# Analog_project.net
KiCad netlist of a schematic drawn in Altium Designer
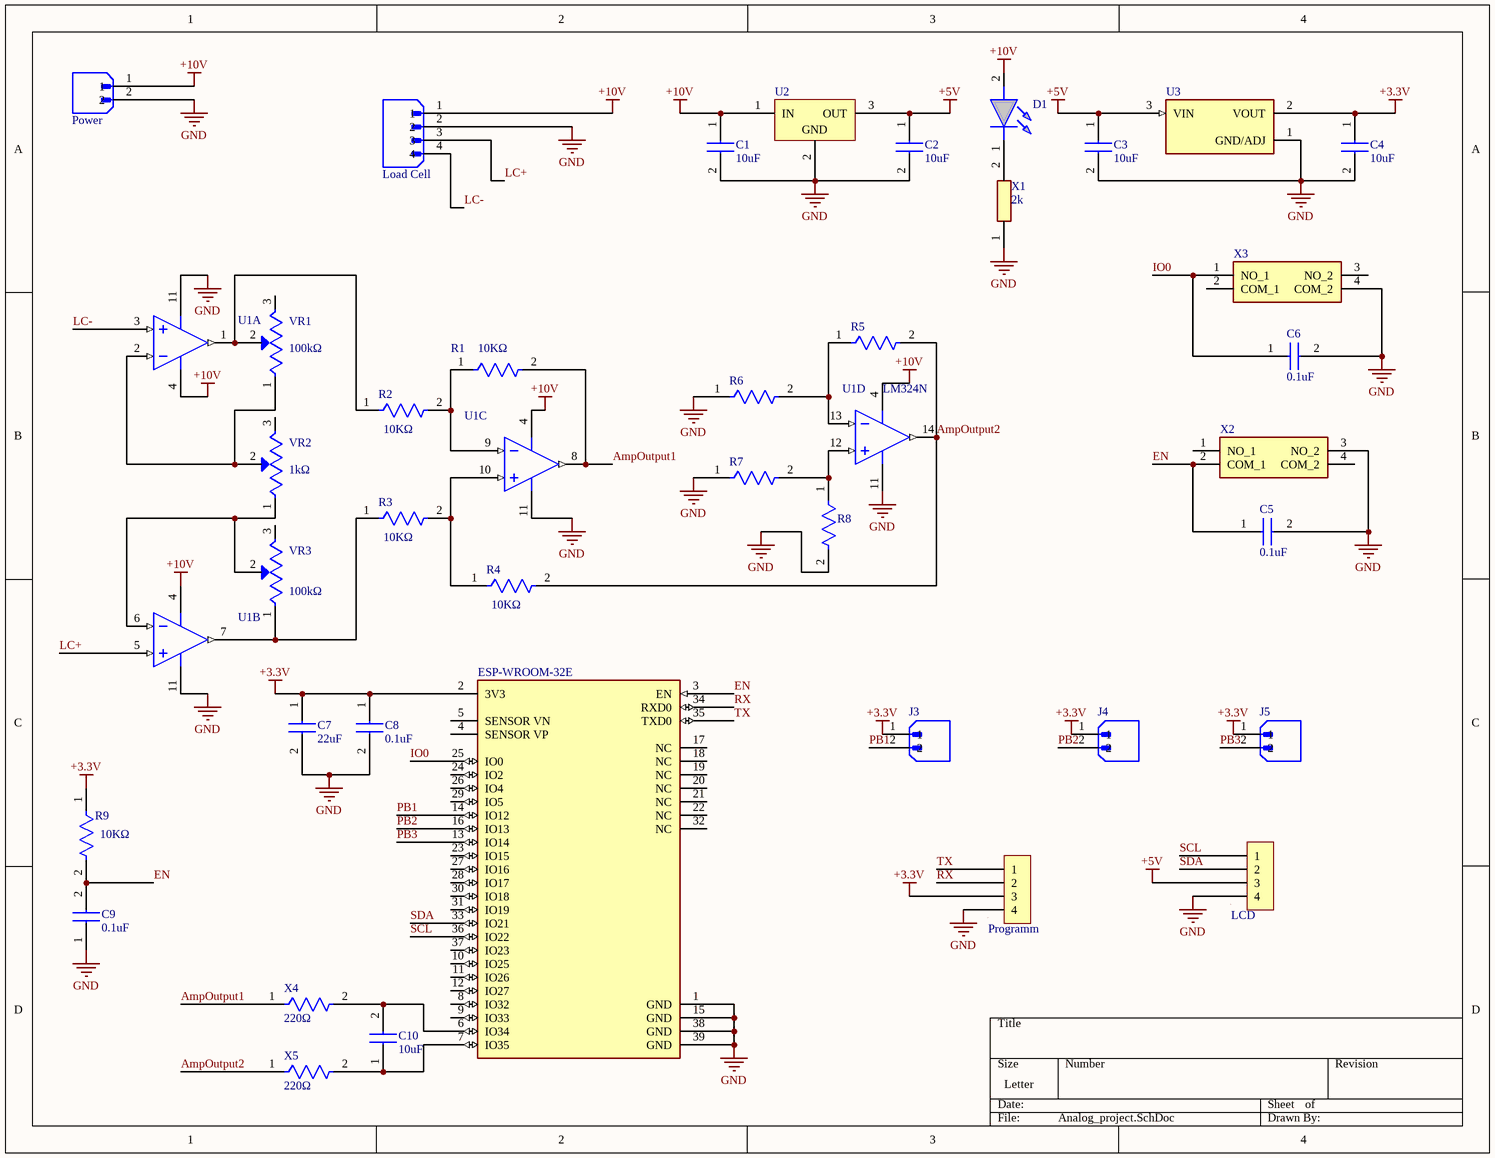
[diagram p0: Analog_project.SchDoc]

(export (version "E")
  (design (tool "Eeschema 10.0.6"))
  (components
    (comp (ref "C1")
      (value "C1206C106K8RAC")
      (footprint "CAPC3216X180N")
      (description "Multilayer Ceramic Capacitors MLCC - SMD/SMT 10V 10uF X7R 1206 0.1")
      (fields (field (name "MOUSER PART NUMBER") "80-C1206C106K8RAC") (field (name "CAPACITANCE") "10uF"))
      (libsource (lib "Analog_project") (part "C1206C106K8RAC"))
    )
    (comp (ref "C2")
      (value "C1206C106K8RAC")
      (footprint "CAPC3216X180N")
      (description "Multilayer Ceramic Capacitors MLCC - SMD/SMT 10V 10uF X7R 1206 0.1")
      (fields (field (name "MOUSER PART NUMBER") "80-C1206C106K8RAC") (field (name "CAPACITANCE") "10uF"))
      (libsource (lib "Analog_project") (part "C1206C106K8RAC"))
    )
    (comp (ref "C3")
      (value "C1206C106K8RAC")
      (footprint "CAPC3216X180N")
      (description "Multilayer Ceramic Capacitors MLCC - SMD/SMT 10V 10uF X7R 1206 0.1")
      (fields (field (name "MOUSER PART NUMBER") "80-C1206C106K8RAC") (field (name "CAPACITANCE") "10uF"))
      (libsource (lib "Analog_project") (part "C1206C106K8RAC"))
    )
    (comp (ref "C4")
      (value "C1206C106K8RAC")
      (footprint "CAPC3216X180N")
      (description "Multilayer Ceramic Capacitors MLCC - SMD/SMT 10V 10uF X7R 1206 0.1")
      (fields (field (name "MOUSER PART NUMBER") "80-C1206C106K8RAC") (field (name "CAPACITANCE") "10uF"))
      (libsource (lib "Analog_project") (part "C1206C106K8RAC"))
    )
    (comp (ref "C5")
      (value "C1206C104K5RAC7867")
      (footprint "CAPC3216X110N")
      (description "Multilayer Ceramic Capacitors MLCC - SMD/SMT 50V 0.1uF X7R 1206 10%")
      (fields (field (name "MOUSER PART NUMBER") "80-C1206104K5RAC7867") (field (name "CAPACITANCE") "0.1uF"))
      (libsource (lib "Analog_project") (part "C1206C104K5RAC7867"))
    )
    (comp (ref "C6")
      (value "C1206C104K5RAC7867")
      (footprint "CAPC3216X110N")
      (description "Multilayer Ceramic Capacitors MLCC - SMD/SMT 50V 0.1uF X7R 1206 10%")
      (fields (field (name "MOUSER PART NUMBER") "80-C1206104K5RAC7867") (field (name "CAPACITANCE") "0.1uF"))
      (libsource (lib "Analog_project") (part "C1206C104K5RAC7867"))
    )
    (comp (ref "C7")
      (value "CL31B226KPKVPJE")
      (footprint "CAPC2012X150N")
      (description "General Multilayer Ceramic Capacitors")
      (fields (field (name "MOUSER PART NUMBER") "187-CL31B226KPKVPJE") (field (name "CAPACITAMCE") "22uF"))
      (libsource (lib "Analog_project") (part "CL31B226KPKVPJE"))
    )
    (comp (ref "C8")
      (value "C1206C104K5RAC7867")
      (footprint "CAPC3216X110N")
      (description "Multilayer Ceramic Capacitors MLCC - SMD/SMT 50V 0.1uF X7R 1206 10%")
      (fields (field (name "MOUSER PART NUMBER") "80-C1206104K5RAC7867") (field (name "CAPACITANCE") "0.1uF"))
      (libsource (lib "Analog_project") (part "C1206C104K5RAC7867"))
    )
    (comp (ref "C9")
      (value "C1206C104K5RAC7867")
      (footprint "CAPC3216X110N")
      (description "Multilayer Ceramic Capacitors MLCC - SMD/SMT 50V 0.1uF X7R 1206 10%")
      (fields (field (name "MOUSER PART NUMBER") "80-C1206104K5RAC7867") (field (name "CAPACITANCE") "0.1uF"))
      (libsource (lib "Analog_project") (part "C1206C104K5RAC7867"))
    )
    (comp (ref "C10")
      (value "C1206C106K8RAC")
      (footprint "CAPC3216X180N")
      (description "Multilayer Ceramic Capacitors MLCC - SMD/SMT 10V 10uF X7R 1206 0.1")
      (fields (field (name "MOUSER PART NUMBER") "80-C1206C106K8RAC") (field (name "CAPACITANCE") "10uF"))
      (libsource (lib "Analog_project") (part "C1206C106K8RAC"))
    )
    (comp (ref "D1")
      (value "150120GS75000")
      (footprint "LEDC3214X78N")
      (fields (field (name "MOUSER PART NUMBER") "710-150120GS75000"))
      (libsource (lib "Analog_project") (part "150120GS75000"))
    )
    (comp (ref "ESP-WROOM-32E")
      (value "ESP32-WROOM-32E (16MB)")
      (footprint "FP-ESP32-WROOM-32E_16MB-MFG")
      (description "RX TXRX MOD WIFI TRACE ANT SMD")
      (libsource (lib "Analog_project") (part "CMP-194065-000027-1"))
    )
    (comp (ref "J3")
      (value "B2B-XH-A(LF)(SN)")
      (footprint "JST_B2B-XH-A(LF)(SN)")
      (description "Connector Header Through Hole 2 position 0.098 (2.50mm)")
      (fields (field (name "MF") "JST Sales America Inc."))
      (libsource (lib "") (part "B2B-XH-A(LF)(SN)_1"))
    )
    (comp (ref "J4")
      (value "B2B-XH-A(LF)(SN)")
      (footprint "JST_B2B-XH-A(LF)(SN)")
      (description "Connector Header Through Hole 2 position 0.098 (2.50mm)")
      (fields (field (name "MF") "JST Sales America Inc."))
      (libsource (lib "") (part "B2B-XH-A(LF)(SN)_1"))
    )
    (comp (ref "J5")
      (value "B2B-XH-A(LF)(SN)")
      (footprint "JST_B2B-XH-A(LF)(SN)")
      (description "Connector Header Through Hole 2 position 0.098 (2.50mm)")
      (fields (field (name "MF") "JST Sales America Inc."))
      (libsource (lib "") (part "B2B-XH-A(LF)(SN)_1"))
    )
    (comp (ref "LCD")
      (value "61300411121")
      (footprint "61300411121")
      (fields (field (name "MANUFACTURER") "Wurth Electronics"))
      (libsource (lib "Analog_project") (part "61300411121"))
    )
    (comp (ref "Load Cell")
      (value "B4B-XH-A(LF)(SN)")
      (footprint "JST_B4B-XH-A(LF)(SN)")
      (description "Connector Header Through Hole 4 position 0.098 (2.50mm)")
      (fields (field (name "MF") "JST Sales"))
      (libsource (lib "Analog_project") (part "B4B-XH-A(LF)(SN)"))
    )
    (comp (ref "Power")
      (value "B2B-XH-A(LF)(SN)")
      (footprint "JST_B2B-XH-A(LF)(SN)")
      (description "Connector Header Through Hole 2 position 0.098 (2.50mm)")
      (fields (field (name "MF") "JST Sales America Inc."))
      (libsource (lib "Analog_project") (part "B2B-XH-A(LF)(SN)"))
    )
    (comp (ref "Programm")
      (value "61300411121")
      (footprint "61300411121")
      (fields (field (name "MANUFACTURER") "Wurth Electronics"))
      (libsource (lib "Analog_project") (part "61300411121"))
    )
    (comp (ref "R1")
      (value "10KΩ")
      (footprint "FP-CRGP1210-IPC_A")
      (description "CRGP1210 10KΩ 0.75W ±100ppm/°C 1% 200V")
      (fields
        (field (name "TOLERANCE") "0.01")
        (field (name "OCTOPART") "https://octopart.com/crgp1210f10k-te+connectivity-91018904")
      )
      (libsource (lib "Analog_project") (part "CMP-03211-008532-1"))
    )
    (comp (ref "R2")
      (value "10KΩ")
      (footprint "FP-CRGP1210-IPC_A")
      (description "CRGP1210 10KΩ 0.75W ±100ppm/°C 1% 200V")
      (fields
        (field (name "TOLERANCE") "0.01")
        (field (name "OCTOPART") "https://octopart.com/crgp1210f10k-te+connectivity-91018904")
      )
      (libsource (lib "Analog_project") (part "CMP-03211-008532-1"))
    )
    (comp (ref "R3")
      (value "10KΩ")
      (footprint "FP-CRGP1210-IPC_A")
      (description "CRGP1210 10KΩ 0.75W ±100ppm/°C 1% 200V")
      (fields
        (field (name "TOLERANCE") "0.01")
        (field (name "OCTOPART") "https://octopart.com/crgp1210f10k-te+connectivity-91018904")
      )
      (libsource (lib "Analog_project") (part "CMP-03211-008532-1"))
    )
    (comp (ref "R4")
      (value "10KΩ")
      (footprint "FP-CRGP1210-IPC_A")
      (description "CRGP1210 10KΩ 0.75W ±100ppm/°C 1% 200V")
      (fields
        (field (name "TOLERANCE") "0.01")
        (field (name "OCTOPART") "https://octopart.com/crgp1210f10k-te+connectivity-91018904")
      )
      (libsource (lib "Analog_project") (part "CMP-03211-008532-1"))
    )
    (comp (ref "R5")
      (value "CRGP1210F10K")
      (footprint "FP-CRGP1210-IPC_A")
      (description "CRGP1210 10KΩ 0.75W ±100ppm/°C 1% 200V")
      (fields
        (field (name "TOLERANCE") "0.01")
        (field (name "OCTOPART") "https://octopart.com/crgp1210f10k-te+connectivity-91018904")
      )
      (libsource (lib "Analog_project") (part "CMP-03211-008532-1"))
    )
    (comp (ref "R6")
      (value "CRGP1210F10K")
      (footprint "FP-CRGP1210-IPC_A")
      (description "CRGP1210 10KΩ 0.75W ±100ppm/°C 1% 200V")
      (fields
        (field (name "TOLERANCE") "0.01")
        (field (name "OCTOPART") "https://octopart.com/crgp1210f10k-te+connectivity-91018904")
      )
      (libsource (lib "Analog_project") (part "CMP-03211-008532-1"))
    )
    (comp (ref "R7")
      (value "CRGP1210F10K")
      (footprint "FP-CRGP1210-IPC_A")
      (description "CRGP1210 10KΩ 0.75W ±100ppm/°C 1% 200V")
      (fields
        (field (name "TOLERANCE") "0.01")
        (field (name "OCTOPART") "https://octopart.com/crgp1210f10k-te+connectivity-91018904")
      )
      (libsource (lib "Analog_project") (part "CMP-03211-008532-1"))
    )
    (comp (ref "R8")
      (value "CRGP1210F10K")
      (footprint "FP-CRGP1210-IPC_A")
      (description "CRGP1210 10KΩ 0.75W ±100ppm/°C 1% 200V")
      (fields
        (field (name "TOLERANCE") "0.01")
        (field (name "OCTOPART") "https://octopart.com/crgp1210f10k-te+connectivity-91018904")
      )
      (libsource (lib "Analog_project") (part "CMP-03211-008532-1"))
    )
    (comp (ref "R9")
      (value "10KΩ")
      (footprint "FP-CRGP1210-IPC_A")
      (description "CRGP1210 10KΩ 0.75W ±100ppm/°C 1% 200V")
      (fields
        (field (name "TOLERANCE") "0.01")
        (field (name "OCTOPART") "https://octopart.com/crgp1210f10k-te+connectivity-91018904")
      )
      (libsource (lib "Analog_project") (part "CMP-03211-008532-1"))
    )
    (comp (ref "U1")
      (value "LM324N")
      (footprint "N0014A")
      (description "Low Power Quad Operational Amplifier, 14-pin MDIP")
      (fields (field (name "MANUFACTURER") "Texas Instruments"))
      (libsource (lib "Analog_project") (part "CMP-0055-00082-3"))
    )
    (comp (ref "U2")
      (value "L7805ACV")
      (footprint "TO220")
      (description "Positive Voltage Regulator, 5V, 3-Pin TO-220")
      (libsource (lib "Analog_project") (part "CMP-0244-00484-1"))
    )
    (comp (ref "U3")
      (value "AMS1117-3.3")
      (footprint "SOT229P700X180-4N")
      (description "Sot223/Pkg 1-Amp 3.3-Volt Low Drop Out Voltage Regulatator")
      (fields (field (name "MF") "Advanced Monolithic Systems"))
      (libsource (lib "Analog_project") (part "AMS1117-3.3"))
    )
    (comp (ref "VR1")
      (value "100kΩ")
      (footprint "TRIM_3296W-OT1-103")
      (fields (field (name "MP") "3296W-OT1-103") (field (name "MF") "Bourns"))
      (libsource (lib "Analog_project") (part "3296W-OT1-103"))
    )
    (comp (ref "VR2")
      (value "1kΩ")
      (footprint "TRIM_3296W-OT1-103")
      (fields (field (name "MP") "3296W-OT1-103") (field (name "MF") "Bourns"))
      (libsource (lib "Analog_project") (part "3296W-OT1-103"))
    )
    (comp (ref "VR3")
      (value "100kΩ")
      (footprint "TRIM_3296W-OT1-103")
      (fields (field (name "MP") "3296W-OT1-103") (field (name "MF") "Bourns"))
      (libsource (lib "Analog_project") (part "3296W-OT1-103"))
    )
    (comp (ref "X1")
      (value "CHP1206AFX-2001ELF")
      (footprint "RESC3116X65X50LL20T20")
      (description "Thick Film Resistors - SMD ResHighPowerA 1206 2k 1% 3/4W TC100 AEC-Q200")
      (fields (field (name "MOUSER PART NUMBER") "652-CHP1206AFX-2001L") (field (name "RESISTANCE") "2k"))
      (libsource (lib "Analog_project") (part "CHP1206AFX-2001ELF"))
    )
    (comp (ref "X2")
      (value "TS04-66-65-BK-160-SMT")
      (footprint "TS046665BK160SMT")
      (description "Tactile Switches 6 x 6 mm, 6.5 mm Act Height, 160 gf, Black, Surface Mount, SPST,")
      (fields (field (name "MOUSER PART NUMBER") "179-TS046665BK160SMT"))
      (libsource (lib "Analog_project") (part "TS04-66-65-BK-160-SMT"))
    )
    (comp (ref "X3")
      (value "TS04-66-65-BK-160-SMT")
      (footprint "TS046665BK160SMT")
      (description "Tactile Switches 6 x 6 mm, 6.5 mm Act Height, 160 gf, Black, Surface Mount, SPST,")
      (fields (field (name "MOUSER PART NUMBER") "179-TS046665BK160SMT"))
      (libsource (lib "Analog_project") (part "TS04-66-65-BK-160-SMT"))
    )
    (comp (ref "X4")
      (value "RCC1206220RFKEA")
      (footprint "RESC3216X60N")
      (description "Thick Film Resistors - SMD 220ohms 1% 100ppm")
      (fields (field (name "MOUSER PART NUMBER") "71-RCC1206220RFKEA") (field (name "RESISTANCE") "220Ω"))
      (libsource (lib "Analog_project") (part "RCC1206220RFKEA"))
    )
    (comp (ref "X5")
      (value "RCC1206220RFKEA")
      (footprint "RESC3216X60N")
      (description "Thick Film Resistors - SMD 220ohms 1% 100ppm")
      (fields (field (name "MOUSER PART NUMBER") "71-RCC1206220RFKEA") (field (name "RESISTANCE") "220Ω"))
      (libsource (lib "Analog_project") (part "RCC1206220RFKEA"))
    )
  )
  (nets
    (net (code "1") (name "+3.3V") (class "Default")
      (node (ref "C4") (pin "1") (pinfunction "1_1") (pintype "passive"))
      (node (ref "C7") (pin "1") (pinfunction "1_1") (pintype "passive"))
      (node (ref "C8") (pin "1") (pinfunction "1_1") (pintype "passive"))
      (node (ref "ESP-WROOM-32E") (pin "2") (pinfunction "3V3_2") (pintype "power_in"))
      (node (ref "J3") (pin "1") (pinfunction "1_1") (pintype "passive"))
      (node (ref "J4") (pin "1") (pinfunction "1_1") (pintype "passive"))
      (node (ref "J5") (pin "1") (pinfunction "1_1") (pintype "passive"))
      (node (ref "Programm") (pin "3") (pinfunction "3_3") (pintype "passive"))
      (node (ref "R9") (pin "1") (pinfunction "1_1") (pintype "passive"))
      (node (ref "U3") (pin "2") (pinfunction "VOUT_2") (pintype "power_in"))
    )
    (net (code "2") (name "+5V") (class "Default")
      (node (ref "C2") (pin "1") (pinfunction "1_1") (pintype "passive"))
      (node (ref "C3") (pin "1") (pinfunction "1_1") (pintype "passive"))
      (node (ref "LCD") (pin "3") (pinfunction "3_3") (pintype "passive"))
      (node (ref "U2") (pin "3") (pinfunction "OUT_3") (pintype "power_in"))
      (node (ref "U3") (pin "3") (pinfunction "VIN_3") (pintype "input"))
    )
    (net (code "3") (name "+10V") (class "Default")
      (node (ref "C1") (pin "1") (pinfunction "1_1") (pintype "passive"))
      (node (ref "D1") (pin "2") (pinfunction "A_2") (pintype "passive"))
      (node (ref "Load Cell") (pin "1") (pinfunction "1_1") (pintype "passive"))
      (node (ref "Power") (pin "1") (pinfunction "1_1") (pintype "passive"))
      (node (ref "U1") (pin "4") (pinfunction "V+_4") (pintype "power_in"))
      (node (ref "U2") (pin "1") (pinfunction "IN_1") (pintype "power_in"))
    )
    (net (code "4") (name "/AmpOutput1") (class "Default")
      (node (ref "R1") (pin "2") (pinfunction "2_2") (pintype "passive"))
      (node (ref "U1") (pin "8") (pinfunction "OUT3_8") (pintype "output"))
      (node (ref "X4") (pin "1") (pinfunction "1_1") (pintype "passive"))
    )
    (net (code "5") (name "/AmpOutput2") (class "Default")
      (node (ref "R4") (pin "2") (pinfunction "2_2") (pintype "passive"))
      (node (ref "R5") (pin "2") (pinfunction "2_2") (pintype "passive"))
      (node (ref "U1") (pin "14") (pinfunction "OUT4_14") (pintype "output"))
      (node (ref "X5") (pin "1") (pinfunction "1_1") (pintype "passive"))
    )
    (net (code "6") (name "/EN") (class "Default")
      (node (ref "C5") (pin "1") (pinfunction "1_1") (pintype "passive"))
      (node (ref "C9") (pin "2") (pinfunction "2_2") (pintype "passive"))
      (node (ref "ESP-WROOM-32E") (pin "3") (pinfunction "EN_3") (pintype "input"))
      (node (ref "R9") (pin "2") (pinfunction "2_2") (pintype "passive"))
      (node (ref "X2") (pin "2") (pinfunction "COM_1_2") (pintype "passive"))
    )
    (net (code "7") (name "/IO0") (class "Default")
      (node (ref "C6") (pin "1") (pinfunction "1_1") (pintype "passive"))
      (node (ref "ESP-WROOM-32E") (pin "25") (pinfunction "IO0_25") (pintype "bidirectional"))
      (node (ref "X3") (pin "1") (pinfunction "NO_1_1") (pintype "passive"))
    )
    (net (code "8") (name "/LC+") (class "Default")
      (node (ref "Load Cell") (pin "3") (pinfunction "3_3") (pintype "passive"))
      (node (ref "U1") (pin "5") (pinfunction "IN2+_5") (pintype "input"))
    )
    (net (code "9") (name "/LC-") (class "Default")
      (node (ref "Load Cell") (pin "4") (pinfunction "4_4") (pintype "passive"))
      (node (ref "U1") (pin "3") (pinfunction "IN1+_3") (pintype "input"))
    )
    (net (code "10") (name "/PB1") (class "Default")
      (node (ref "ESP-WROOM-32E") (pin "14") (pinfunction "IO12_14") (pintype "bidirectional"))
      (node (ref "J3") (pin "2") (pinfunction "2_2") (pintype "passive"))
    )
    (net (code "11") (name "/PB2") (class "Default")
      (node (ref "ESP-WROOM-32E") (pin "16") (pinfunction "IO13_16") (pintype "bidirectional"))
      (node (ref "J4") (pin "2") (pinfunction "2_2") (pintype "passive"))
    )
    (net (code "12") (name "/PB3") (class "Default")
      (node (ref "ESP-WROOM-32E") (pin "13") (pinfunction "IO14_13") (pintype "bidirectional"))
      (node (ref "J5") (pin "2") (pinfunction "2_2") (pintype "passive"))
    )
    (net (code "13") (name "/RX") (class "Default")
      (node (ref "ESP-WROOM-32E") (pin "34") (pinfunction "RXD0_34") (pintype "bidirectional"))
      (node (ref "Programm") (pin "2") (pinfunction "2_2") (pintype "passive"))
    )
    (net (code "14") (name "/SCL") (class "Default")
      (node (ref "ESP-WROOM-32E") (pin "36") (pinfunction "IO22_36") (pintype "bidirectional"))
      (node (ref "LCD") (pin "1") (pinfunction "1_1") (pintype "passive"))
    )
    (net (code "15") (name "/SDA") (class "Default")
      (node (ref "ESP-WROOM-32E") (pin "33") (pinfunction "IO21_33") (pintype "bidirectional"))
      (node (ref "LCD") (pin "2") (pinfunction "2_2") (pintype "passive"))
    )
    (net (code "16") (name "/TX") (class "Default")
      (node (ref "ESP-WROOM-32E") (pin "35") (pinfunction "TXD0_35") (pintype "bidirectional"))
      (node (ref "Programm") (pin "1") (pinfunction "1_1") (pintype "passive"))
    )
    (net (code "17") (name "GND") (class "Default")
      (node (ref "C1") (pin "2") (pinfunction "2_2") (pintype "passive"))
      (node (ref "C2") (pin "2") (pinfunction "2_2") (pintype "passive"))
      (node (ref "C3") (pin "2") (pinfunction "2_2") (pintype "passive"))
      (node (ref "C4") (pin "2") (pinfunction "2_2") (pintype "passive"))
      (node (ref "C5") (pin "2") (pinfunction "2_2") (pintype "passive"))
      (node (ref "C6") (pin "2") (pinfunction "2_2") (pintype "passive"))
      (node (ref "C7") (pin "2") (pinfunction "2_2") (pintype "passive"))
      (node (ref "C8") (pin "2") (pinfunction "2_2") (pintype "passive"))
      (node (ref "C9") (pin "1") (pinfunction "1_1") (pintype "passive"))
      (node (ref "ESP-WROOM-32E") (pin "1") (pinfunction "GND_1") (pintype "power_in"))
      (node (ref "ESP-WROOM-32E") (pin "15") (pinfunction "GND_15") (pintype "power_in"))
      (node (ref "ESP-WROOM-32E") (pin "38") (pinfunction "GND_38") (pintype "power_in"))
      (node (ref "ESP-WROOM-32E") (pin "39") (pinfunction "GND_39") (pintype "power_in"))
      (node (ref "LCD") (pin "4") (pinfunction "4_4") (pintype "passive"))
      (node (ref "Load Cell") (pin "2") (pinfunction "2_2") (pintype "passive"))
      (node (ref "Power") (pin "2") (pinfunction "2_2") (pintype "passive"))
      (node (ref "Programm") (pin "4") (pinfunction "4_4") (pintype "passive"))
      (node (ref "R6") (pin "1") (pinfunction "1_1") (pintype "passive"))
      (node (ref "R7") (pin "1") (pinfunction "1_1") (pintype "passive"))
      (node (ref "R8") (pin "2") (pinfunction "2_2") (pintype "passive"))
      (node (ref "U1") (pin "11") (pinfunction "GND_11") (pintype "power_in"))
      (node (ref "U2") (pin "2") (pinfunction "GND_2") (pintype "power_in"))
      (node (ref "U3") (pin "1") (pinfunction "GND/ADJ_1") (pintype "power_in"))
      (node (ref "X1") (pin "1") (pinfunction "1_1") (pintype "passive"))
      (node (ref "X2") (pin "3") (pinfunction "NO_2_3") (pintype "passive"))
      (node (ref "X3") (pin "4") (pinfunction "COM_2_4") (pintype "passive"))
    )
    (net (code "18") (name "Net-(D1-K)") (class "Default")
      (node (ref "D1") (pin "1") (pinfunction "K_1") (pintype "passive"))
      (node (ref "X1") (pin "2") (pinfunction "2_2") (pintype "passive"))
    )
    (net (code "19") (name "Net-(ESP-WROOM-32E-IO34)") (class "Default")
      (node (ref "C10") (pin "2") (pinfunction "2_2") (pintype "passive"))
      (node (ref "ESP-WROOM-32E") (pin "6") (pinfunction "IO34_6") (pintype "bidirectional"))
      (node (ref "X4") (pin "2") (pinfunction "2_2") (pintype "passive"))
    )
    (net (code "20") (name "Net-(ESP-WROOM-32E-IO35)") (class "Default")
      (node (ref "C10") (pin "1") (pinfunction "1_1") (pintype "passive"))
      (node (ref "ESP-WROOM-32E") (pin "7") (pinfunction "IO35_7") (pintype "bidirectional"))
      (node (ref "X5") (pin "2") (pinfunction "2_2") (pintype "passive"))
    )
    (net (code "21") (name "Net-(U1A-IN1-)") (class "Default")
      (node (ref "U1") (pin "2") (pinfunction "IN1-_2") (pintype "input"))
      (node (ref "VR1") (pin "1") (pinfunction "CCW_1") (pintype "passive"))
      (node (ref "VR2") (pin "2") (pinfunction "WIPER_2") (pintype "passive"))
    )
    (net (code "22") (name "Net-(U1A-OUT1)") (class "Default")
      (node (ref "R2") (pin "1") (pinfunction "1_1") (pintype "passive"))
      (node (ref "U1") (pin "1") (pinfunction "OUT1_1") (pintype "output"))
      (node (ref "VR1") (pin "2") (pinfunction "WIPER_2") (pintype "passive"))
    )
    (net (code "23") (name "Net-(U1B-IN2-)") (class "Default")
      (node (ref "U1") (pin "6") (pinfunction "IN2-_6") (pintype "input"))
      (node (ref "VR2") (pin "1") (pinfunction "CCW_1") (pintype "passive"))
      (node (ref "VR3") (pin "2") (pinfunction "WIPER_2") (pintype "passive"))
    )
    (net (code "24") (name "Net-(U1B-OUT2)") (class "Default")
      (node (ref "R3") (pin "1") (pinfunction "1_1") (pintype "passive"))
      (node (ref "U1") (pin "7") (pinfunction "OUT2_7") (pintype "output"))
      (node (ref "VR3") (pin "1") (pinfunction "CCW_1") (pintype "passive"))
    )
    (net (code "25") (name "Net-(U1C-IN3+)") (class "Default")
      (node (ref "R3") (pin "2") (pinfunction "2_2") (pintype "passive"))
      (node (ref "R4") (pin "1") (pinfunction "1_1") (pintype "passive"))
      (node (ref "U1") (pin "10") (pinfunction "IN3+_10") (pintype "input"))
    )
    (net (code "26") (name "Net-(U1C-IN3-)") (class "Default")
      (node (ref "R1") (pin "1") (pinfunction "1_1") (pintype "passive"))
      (node (ref "R2") (pin "2") (pinfunction "2_2") (pintype "passive"))
      (node (ref "U1") (pin "9") (pinfunction "IN3-_9") (pintype "input"))
    )
    (net (code "27") (name "Net-(U1D-IN4+)") (class "Default")
      (node (ref "R7") (pin "2") (pinfunction "2_2") (pintype "passive"))
      (node (ref "R8") (pin "1") (pinfunction "1_1") (pintype "passive"))
      (node (ref "U1") (pin "12") (pinfunction "IN4+_12") (pintype "input"))
    )
    (net (code "28") (name "Net-(U1D-IN4-)") (class "Default")
      (node (ref "R5") (pin "1") (pinfunction "1_1") (pintype "passive"))
      (node (ref "R6") (pin "2") (pinfunction "2_2") (pintype "passive"))
      (node (ref "U1") (pin "13") (pinfunction "IN4-_13") (pintype "input"))
    )
    (net (code "29") (name "unconnected-(ESP-WROOM-32E-IO2-Pad24)") (class "Default")
      (node (ref "ESP-WROOM-32E") (pin "24") (pinfunction "IO2_24") (pintype "bidirectional"))
    )
    (net (code "30") (name "unconnected-(ESP-WROOM-32E-IO4-Pad26)") (class "Default")
      (node (ref "ESP-WROOM-32E") (pin "26") (pinfunction "IO4_26") (pintype "bidirectional"))
    )
    (net (code "31") (name "unconnected-(ESP-WROOM-32E-IO5-Pad29)") (class "Default")
      (node (ref "ESP-WROOM-32E") (pin "29") (pinfunction "IO5_29") (pintype "bidirectional"))
    )
    (net (code "32") (name "unconnected-(ESP-WROOM-32E-IO15-Pad23)") (class "Default")
      (node (ref "ESP-WROOM-32E") (pin "23") (pinfunction "IO15_23") (pintype "bidirectional"))
    )
    (net (code "33") (name "unconnected-(ESP-WROOM-32E-IO16-Pad27)") (class "Default")
      (node (ref "ESP-WROOM-32E") (pin "27") (pinfunction "IO16_27") (pintype "bidirectional"))
    )
    (net (code "34") (name "unconnected-(ESP-WROOM-32E-IO17-Pad28)") (class "Default")
      (node (ref "ESP-WROOM-32E") (pin "28") (pinfunction "IO17_28") (pintype "bidirectional"))
    )
    (net (code "35") (name "unconnected-(ESP-WROOM-32E-IO18-Pad30)") (class "Default")
      (node (ref "ESP-WROOM-32E") (pin "30") (pinfunction "IO18_30") (pintype "bidirectional"))
    )
    (net (code "36") (name "unconnected-(ESP-WROOM-32E-IO19-Pad31)") (class "Default")
      (node (ref "ESP-WROOM-32E") (pin "31") (pinfunction "IO19_31") (pintype "bidirectional"))
    )
    (net (code "37") (name "unconnected-(ESP-WROOM-32E-IO23-Pad37)") (class "Default")
      (node (ref "ESP-WROOM-32E") (pin "37") (pinfunction "IO23_37") (pintype "bidirectional"))
    )
    (net (code "38") (name "unconnected-(ESP-WROOM-32E-IO25-Pad10)") (class "Default")
      (node (ref "ESP-WROOM-32E") (pin "10") (pinfunction "IO25_10") (pintype "bidirectional"))
    )
    (net (code "39") (name "unconnected-(ESP-WROOM-32E-IO26-Pad11)") (class "Default")
      (node (ref "ESP-WROOM-32E") (pin "11") (pinfunction "IO26_11") (pintype "bidirectional"))
    )
    (net (code "40") (name "unconnected-(ESP-WROOM-32E-IO27-Pad12)") (class "Default")
      (node (ref "ESP-WROOM-32E") (pin "12") (pinfunction "IO27_12") (pintype "bidirectional"))
    )
    (net (code "41") (name "unconnected-(ESP-WROOM-32E-IO32-Pad8)") (class "Default")
      (node (ref "ESP-WROOM-32E") (pin "8") (pinfunction "IO32_8") (pintype "bidirectional"))
    )
    (net (code "42") (name "unconnected-(ESP-WROOM-32E-IO33-Pad9)") (class "Default")
      (node (ref "ESP-WROOM-32E") (pin "9") (pinfunction "IO33_9") (pintype "bidirectional"))
    )
    (net (code "43") (name "unconnected-(ESP-WROOM-32E-NC-Pad17)") (class "Default")
      (node (ref "ESP-WROOM-32E") (pin "17") (pinfunction "NC_17") (pintype "passive"))
    )
    (net (code "44") (name "unconnected-(ESP-WROOM-32E-NC-Pad18)") (class "Default")
      (node (ref "ESP-WROOM-32E") (pin "18") (pinfunction "NC_18") (pintype "passive"))
    )
    (net (code "45") (name "unconnected-(ESP-WROOM-32E-NC-Pad19)") (class "Default")
      (node (ref "ESP-WROOM-32E") (pin "19") (pinfunction "NC_19") (pintype "passive"))
    )
    (net (code "46") (name "unconnected-(ESP-WROOM-32E-NC-Pad20)") (class "Default")
      (node (ref "ESP-WROOM-32E") (pin "20") (pinfunction "NC_20") (pintype "passive"))
    )
    (net (code "47") (name "unconnected-(ESP-WROOM-32E-NC-Pad21)") (class "Default")
      (node (ref "ESP-WROOM-32E") (pin "21") (pinfunction "NC_21") (pintype "passive"))
    )
    (net (code "48") (name "unconnected-(ESP-WROOM-32E-NC-Pad22)") (class "Default")
      (node (ref "ESP-WROOM-32E") (pin "22") (pinfunction "NC_22") (pintype "passive"))
    )
    (net (code "49") (name "unconnected-(ESP-WROOM-32E-NC-Pad32)") (class "Default")
      (node (ref "ESP-WROOM-32E") (pin "32") (pinfunction "NC_32") (pintype "passive"))
    )
    (net (code "50") (name "unconnected-(ESP-WROOM-32E-SENSOR_VN-Pad5)") (class "Default")
      (node (ref "ESP-WROOM-32E") (pin "5") (pinfunction "SENSOR_VN_5") (pintype "passive"))
    )
    (net (code "51") (name "unconnected-(ESP-WROOM-32E-SENSOR_VP-Pad4)") (class "Default")
      (node (ref "ESP-WROOM-32E") (pin "4") (pinfunction "SENSOR_VP_4") (pintype "passive"))
    )
    (net (code "52") (name "unconnected-(VR1-CW-Pad3)") (class "Default")
      (node (ref "VR1") (pin "3") (pinfunction "CW_3") (pintype "passive"))
    )
    (net (code "53") (name "unconnected-(VR2-CW-Pad3)") (class "Default")
      (node (ref "VR2") (pin "3") (pinfunction "CW_3") (pintype "passive"))
    )
    (net (code "54") (name "unconnected-(VR3-CW-Pad3)") (class "Default")
      (node (ref "VR3") (pin "3") (pinfunction "CW_3") (pintype "passive"))
    )
    (net (code "55") (name "unconnected-(X2-COM_2-Pad4)") (class "Default")
      (node (ref "X2") (pin "4") (pinfunction "COM_2_4") (pintype "passive"))
    )
    (net (code "56") (name "unconnected-(X2-NO_1-Pad1)") (class "Default")
      (node (ref "X2") (pin "1") (pinfunction "NO_1_1") (pintype "passive"))
    )
    (net (code "57") (name "unconnected-(X3-COM_1-Pad2)") (class "Default")
      (node (ref "X3") (pin "2") (pinfunction "COM_1_2") (pintype "passive"))
    )
    (net (code "58") (name "unconnected-(X3-NO_2-Pad3)") (class "Default")
      (node (ref "X3") (pin "3") (pinfunction "NO_2_3") (pintype "passive"))
    )
  )
)
